# LED_Array.net
KiCad netlist of a schematic drawn in Altium Designer
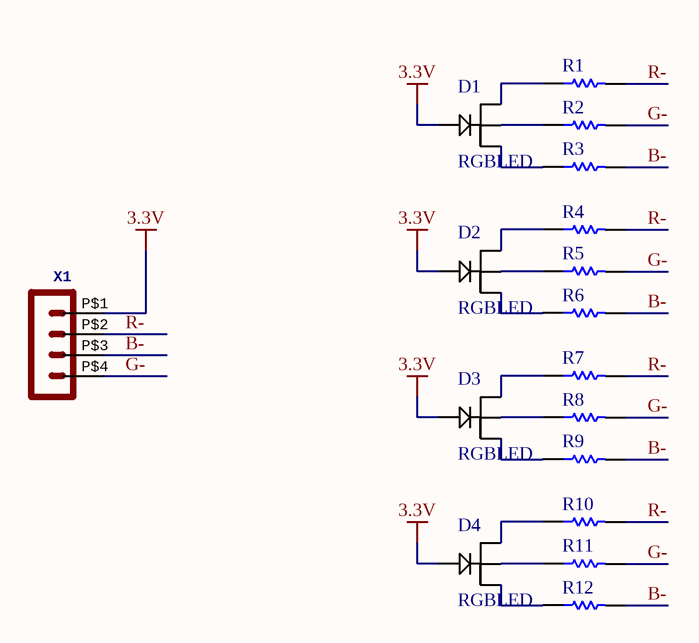
[diagram p0: LED_Array.SchDoc]

(export (version "E")
  (design (tool "Eeschema 10.0.6"))
  (components
    (comp (ref "D1")
      (value "RGBLED")
      (footprint "RGBLED")
      (libsource (lib "RoverTransistors") (part "RGBLED"))
    )
    (comp (ref "D2")
      (value "RGBLED")
      (footprint "RGBLED")
      (libsource (lib "RoverTransistors") (part "RGBLED"))
    )
    (comp (ref "D3")
      (value "RGBLED")
      (footprint "RGBLED")
      (libsource (lib "RoverTransistors") (part "RGBLED"))
    )
    (comp (ref "D4")
      (value "RGBLED")
      (footprint "RGBLED")
      (libsource (lib "RoverTransistors") (part "RGBLED"))
    )
    (comp (ref "R1")
      (value "Res1")
      (footprint "AXIAL-0.3")
      (description "Resistor")
      (fields (field (name "PUBLISHER") "Altium Limited"))
      (libsource (lib "Miscellaneous Devices") (part "Res1"))
    )
    (comp (ref "R2")
      (value "Res1")
      (footprint "AXIAL-0.3")
      (description "Resistor")
      (fields (field (name "PUBLISHER") "Altium Limited"))
      (libsource (lib "Miscellaneous Devices") (part "Res1"))
    )
    (comp (ref "R3")
      (value "Res1")
      (footprint "AXIAL-0.3")
      (description "Resistor")
      (fields (field (name "PUBLISHER") "Altium Limited"))
      (libsource (lib "Miscellaneous Devices") (part "Res1"))
    )
    (comp (ref "R4")
      (value "Res1")
      (footprint "AXIAL-0.3")
      (description "Resistor")
      (fields (field (name "PUBLISHER") "Altium Limited"))
      (libsource (lib "Miscellaneous Devices") (part "Res1"))
    )
    (comp (ref "R5")
      (value "Res1")
      (footprint "AXIAL-0.3")
      (description "Resistor")
      (fields (field (name "PUBLISHER") "Altium Limited"))
      (libsource (lib "Miscellaneous Devices") (part "Res1"))
    )
    (comp (ref "R6")
      (value "Res1")
      (footprint "AXIAL-0.3")
      (description "Resistor")
      (fields (field (name "PUBLISHER") "Altium Limited"))
      (libsource (lib "Miscellaneous Devices") (part "Res1"))
    )
    (comp (ref "R7")
      (value "Res1")
      (footprint "AXIAL-0.3")
      (description "Resistor")
      (fields (field (name "PUBLISHER") "Altium Limited"))
      (libsource (lib "Miscellaneous Devices") (part "Res1"))
    )
    (comp (ref "R8")
      (value "Res1")
      (footprint "AXIAL-0.3")
      (description "Resistor")
      (fields (field (name "PUBLISHER") "Altium Limited"))
      (libsource (lib "Miscellaneous Devices") (part "Res1"))
    )
    (comp (ref "R9")
      (value "Res1")
      (footprint "AXIAL-0.3")
      (description "Resistor")
      (fields (field (name "PUBLISHER") "Altium Limited"))
      (libsource (lib "Miscellaneous Devices") (part "Res1"))
    )
    (comp (ref "R10")
      (value "Res1")
      (footprint "AXIAL-0.3")
      (description "Resistor")
      (fields (field (name "PUBLISHER") "Altium Limited"))
      (libsource (lib "Miscellaneous Devices") (part "Res1"))
    )
    (comp (ref "R11")
      (value "Res1")
      (footprint "AXIAL-0.3")
      (description "Resistor")
      (fields (field (name "PUBLISHER") "Altium Limited"))
      (libsource (lib "Miscellaneous Devices") (part "Res1"))
    )
    (comp (ref "R12")
      (value "Res1")
      (footprint "AXIAL-0.3")
      (description "Resistor")
      (fields (field (name "PUBLISHER") "Altium Limited"))
      (libsource (lib "Miscellaneous Devices") (part "Res1"))
    )
    (comp (ref "X1")
      (value "Molex - Micro-Fit 3.0 Series connector,  3.00mm (0.118\") pitch header, 4 positions.")
      (footprint "43650-0400")
      (libsource (lib "Molex Microfit") (part "HEADER_POS4_?43650-0400"))
    )
  )
  (nets
    (net (code "1") (name "/B-") (class "Default")
      (node (ref "R12") (pin "2") (pinfunction "2_2") (pintype "passive"))
      (node (ref "R3") (pin "2") (pinfunction "2_2") (pintype "passive"))
      (node (ref "R6") (pin "2") (pinfunction "2_2") (pintype "passive"))
      (node (ref "R9") (pin "2") (pinfunction "2_2") (pintype "passive"))
      (node (ref "X1") (pin "P$3") (pinfunction "3_P$3") (pintype "passive"))
    )
    (net (code "2") (name "/G-") (class "Default")
      (node (ref "R11") (pin "2") (pinfunction "2_2") (pintype "passive"))
      (node (ref "R2") (pin "2") (pinfunction "2_2") (pintype "passive"))
      (node (ref "R5") (pin "2") (pinfunction "2_2") (pintype "passive"))
      (node (ref "R8") (pin "2") (pinfunction "2_2") (pintype "passive"))
      (node (ref "X1") (pin "P$4") (pinfunction "4_P$4") (pintype "passive"))
    )
    (net (code "3") (name "/R-") (class "Default")
      (node (ref "R1") (pin "2") (pinfunction "2_2") (pintype "passive"))
      (node (ref "R10") (pin "2") (pinfunction "2_2") (pintype "passive"))
      (node (ref "R4") (pin "2") (pinfunction "2_2") (pintype "passive"))
      (node (ref "R7") (pin "2") (pinfunction "2_2") (pintype "passive"))
      (node (ref "X1") (pin "P$2") (pinfunction "1_P$2") (pintype "passive"))
    )
    (net (code "4") (name "3.3V") (class "Default")
      (node (ref "D1") (pin "0") (pinfunction "7_0") (pintype "passive"))
      (node (ref "D2") (pin "0") (pinfunction "7_0") (pintype "passive"))
      (node (ref "D3") (pin "0") (pinfunction "7_0") (pintype "passive"))
      (node (ref "D4") (pin "0") (pinfunction "7_0") (pintype "passive"))
      (node (ref "X1") (pin "P$1") (pinfunction "2_P$1") (pintype "passive"))
    )
    (net (code "5") (name "Net-(D1-B-)") (class "Default")
      (node (ref "D1") (pin "3") (pinfunction "B-_3") (pintype "passive"))
      (node (ref "R3") (pin "1") (pinfunction "1_1") (pintype "passive"))
    )
    (net (code "6") (name "Net-(D1-G-)") (class "Default")
      (node (ref "D1") (pin "2") (pinfunction "G-_2") (pintype "passive"))
      (node (ref "R2") (pin "1") (pinfunction "1_1") (pintype "passive"))
    )
    (net (code "7") (name "Net-(D1-R-)") (class "Default")
      (node (ref "D1") (pin "1") (pinfunction "R-_1") (pintype "passive"))
      (node (ref "R1") (pin "1") (pinfunction "1_1") (pintype "passive"))
    )
    (net (code "8") (name "Net-(D2-B-)") (class "Default")
      (node (ref "D2") (pin "3") (pinfunction "B-_3") (pintype "passive"))
      (node (ref "R6") (pin "1") (pinfunction "1_1") (pintype "passive"))
    )
    (net (code "9") (name "Net-(D2-G-)") (class "Default")
      (node (ref "D2") (pin "2") (pinfunction "G-_2") (pintype "passive"))
      (node (ref "R5") (pin "1") (pinfunction "1_1") (pintype "passive"))
    )
    (net (code "10") (name "Net-(D2-R-)") (class "Default")
      (node (ref "D2") (pin "1") (pinfunction "R-_1") (pintype "passive"))
      (node (ref "R4") (pin "1") (pinfunction "1_1") (pintype "passive"))
    )
    (net (code "11") (name "Net-(D3-B-)") (class "Default")
      (node (ref "D3") (pin "3") (pinfunction "B-_3") (pintype "passive"))
      (node (ref "R9") (pin "1") (pinfunction "1_1") (pintype "passive"))
    )
    (net (code "12") (name "Net-(D3-G-)") (class "Default")
      (node (ref "D3") (pin "2") (pinfunction "G-_2") (pintype "passive"))
      (node (ref "R8") (pin "1") (pinfunction "1_1") (pintype "passive"))
    )
    (net (code "13") (name "Net-(D3-R-)") (class "Default")
      (node (ref "D3") (pin "1") (pinfunction "R-_1") (pintype "passive"))
      (node (ref "R7") (pin "1") (pinfunction "1_1") (pintype "passive"))
    )
    (net (code "14") (name "Net-(D4-B-)") (class "Default")
      (node (ref "D4") (pin "3") (pinfunction "B-_3") (pintype "passive"))
      (node (ref "R12") (pin "1") (pinfunction "1_1") (pintype "passive"))
    )
    (net (code "15") (name "Net-(D4-G-)") (class "Default")
      (node (ref "D4") (pin "2") (pinfunction "G-_2") (pintype "passive"))
      (node (ref "R11") (pin "1") (pinfunction "1_1") (pintype "passive"))
    )
    (net (code "16") (name "Net-(D4-R-)") (class "Default")
      (node (ref "D4") (pin "1") (pinfunction "R-_1") (pintype "passive"))
      (node (ref "R10") (pin "1") (pinfunction "1_1") (pintype "passive"))
    )
  )
)
